# Light.net
KiCad netlist of a schematic drawn in Altium Designer
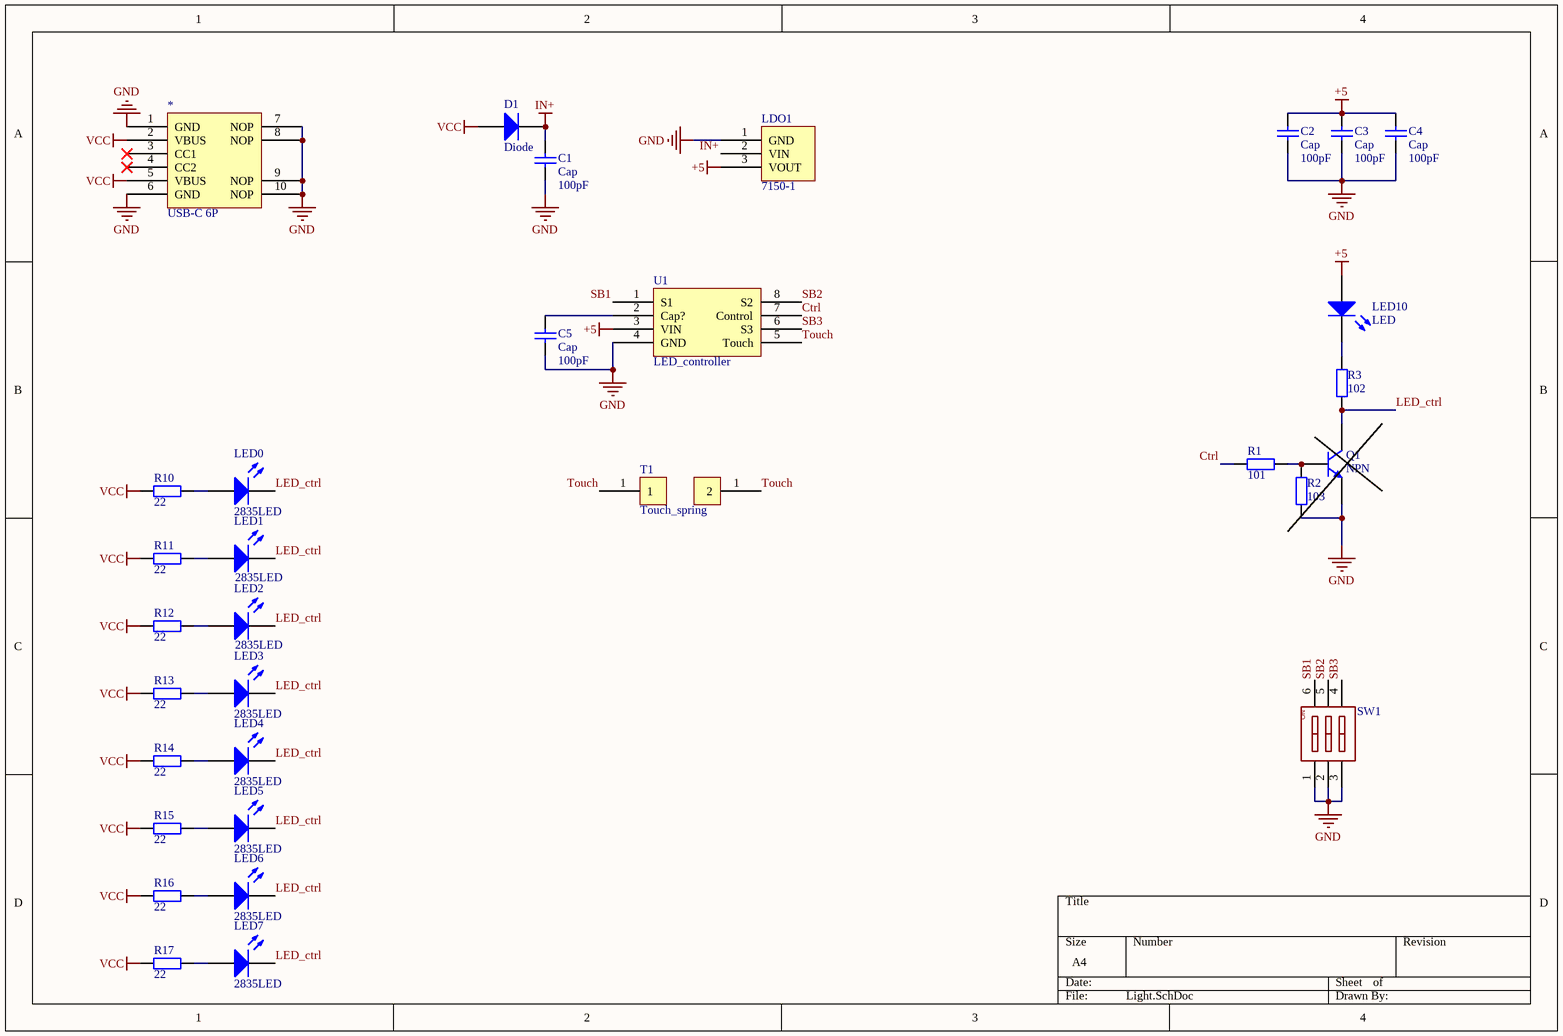
[diagram p0: Light.SchDoc]

(export (version "E")
  (design (tool "Eeschema 10.0.6"))
  (components
    (comp (ref "*") (value "USB-C 6P") (footprint "USB-C 6P") (libsource (lib "USB") (part "USB-C 6P")))
    (comp (ref "C1")
      (value "Cap")
      (footprint "6-0805_M")
      (description "Capacitor")
      (fields (field (name "ALTIUM_VALUE") "100pF") (field (name "PUBLISHER") "Altium Limited"))
      (libsource (lib "Miscellaneous Devices") (part "Cap"))
    )
    (comp (ref "C2")
      (value "Cap")
      (footprint "1608[0603]")
      (description "Capacitor")
      (fields (field (name "ALTIUM_VALUE") "100pF") (field (name "PUBLISHER") "Altium Limited"))
      (libsource (lib "Miscellaneous Devices") (part "Cap"))
    )
    (comp (ref "C3")
      (value "Cap")
      (footprint "1608[0603]")
      (description "Capacitor")
      (fields (field (name "ALTIUM_VALUE") "100pF") (field (name "PUBLISHER") "Altium Limited"))
      (libsource (lib "Miscellaneous Devices") (part "Cap"))
    )
    (comp (ref "C4")
      (value "Cap")
      (footprint "1608[0603]")
      (description "Capacitor")
      (fields (field (name "ALTIUM_VALUE") "100pF") (field (name "PUBLISHER") "Altium Limited"))
      (libsource (lib "Miscellaneous Devices") (part "Cap"))
    )
    (comp (ref "C5")
      (value "Cap")
      (footprint "1608[0603]")
      (description "Capacitor")
      (fields (field (name "ALTIUM_VALUE") "100pF") (field (name "PUBLISHER") "Altium Limited"))
      (libsource (lib "Miscellaneous Devices") (part "Cap"))
    )
    (comp (ref "D1")
      (value "Diode")
      (footprint "SOD-123")
      (description "Default Diode")
      (fields (field (name "PUBLISHER") "Altium Limited"))
      (libsource (lib "Miscellaneous Devices") (part "Diode"))
    )
    (comp (ref "LDO1")
      (value "7150-1")
      (footprint "SOT-89")
      (libsource (lib "Common_Modules") (part "7150-1"))
    )
    (comp (ref "LED0")
      (value "2835LED")
      (footprint "2835LED")
      (libsource (lib "Common_Modules") (part "2835LED"))
    )
    (comp (ref "LED1")
      (value "2835LED")
      (footprint "2835LED")
      (libsource (lib "Common_Modules") (part "2835LED"))
    )
    (comp (ref "LED2")
      (value "2835LED")
      (footprint "2835LED")
      (libsource (lib "Common_Modules") (part "2835LED"))
    )
    (comp (ref "LED3")
      (value "2835LED")
      (footprint "2835LED")
      (libsource (lib "Common_Modules") (part "2835LED"))
    )
    (comp (ref "LED4")
      (value "2835LED")
      (footprint "2835LED")
      (libsource (lib "Common_Modules") (part "2835LED"))
    )
    (comp (ref "LED5")
      (value "2835LED")
      (footprint "2835LED")
      (libsource (lib "Common_Modules") (part "2835LED"))
    )
    (comp (ref "LED6")
      (value "2835LED")
      (footprint "2835LED")
      (libsource (lib "Common_Modules") (part "2835LED"))
    )
    (comp (ref "LED7")
      (value "2835LED")
      (footprint "2835LED")
      (libsource (lib "Common_Modules") (part "2835LED"))
    )
    (comp (ref "LED10")
      (value "LED")
      (footprint "LED")
      (description "Typical INFRARED GaAs LED")
      (fields (field (name "PUBLISHER") "Altium Limited"))
      (libsource (lib "Miscellaneous Devices") (part "LED"))
    )
    (comp (ref "Q1")
      (value "NPN")
      (footprint "SOT23")
      (description "NPN Bipolar Transistor")
      (fields (field (name "PUBLISHER") "Altium Limited"))
      (libsource (lib "Miscellaneous Devices") (part "NPN"))
    )
    (comp (ref "R1")
      (value "101")
      (footprint "1608[0603]")
      (description "Resistor")
      (fields (field (name "PUBLISHER") "Altium Limited"))
      (libsource (lib "") (part "Res_1"))
    )
    (comp (ref "R2")
      (value "103")
      (footprint "1608[0603]")
      (description "Resistor")
      (fields (field (name "PUBLISHER") "Altium Limited"))
      (libsource (lib "Miscellaneous Devices") (part "Res"))
    )
    (comp (ref "R3")
      (value "102")
      (footprint "1608[0603]")
      (description "Resistor")
      (fields (field (name "PUBLISHER") "Altium Limited"))
      (libsource (lib "") (part "Res_2"))
    )
    (comp (ref "R10")
      (value "22")
      (footprint "R1206")
      (description "Resistor")
      (fields (field (name "PUBLISHER") "Altium Limited"))
      (libsource (lib "") (part "Res_1"))
    )
    (comp (ref "R11")
      (value "22")
      (footprint "R1206")
      (description "Resistor")
      (fields (field (name "PUBLISHER") "Altium Limited"))
      (libsource (lib "") (part "Res_1"))
    )
    (comp (ref "R12")
      (value "22")
      (footprint "R1206")
      (description "Resistor")
      (fields (field (name "PUBLISHER") "Altium Limited"))
      (libsource (lib "") (part "Res_1"))
    )
    (comp (ref "R13")
      (value "22")
      (footprint "R1206")
      (description "Resistor")
      (fields (field (name "PUBLISHER") "Altium Limited"))
      (libsource (lib "") (part "Res_1"))
    )
    (comp (ref "R14")
      (value "22")
      (footprint "R1206")
      (description "Resistor")
      (fields (field (name "PUBLISHER") "Altium Limited"))
      (libsource (lib "") (part "Res_1"))
    )
    (comp (ref "R15")
      (value "22")
      (footprint "R1206")
      (description "Resistor")
      (fields (field (name "PUBLISHER") "Altium Limited"))
      (libsource (lib "") (part "Res_1"))
    )
    (comp (ref "R16")
      (value "22")
      (footprint "R1206")
      (description "Resistor")
      (fields (field (name "PUBLISHER") "Altium Limited"))
      (libsource (lib "") (part "Res_1"))
    )
    (comp (ref "R17")
      (value "22")
      (footprint "R1206")
      (description "Resistor")
      (fields (field (name "PUBLISHER") "Altium Limited"))
      (libsource (lib "") (part "Res_1"))
    )
    (comp (ref "SW1")
      (value "SD03H0SB")
      (footprint "SW-SMD_3")
      (libsource (lib "Miscellaneous Devices") (part "SW Dial-3"))
    )
    (comp (ref "T1")
      (value "Touch_spring")
      (footprint "Touch_spring2")
      (libsource (lib "Connectivity_pads") (part "Touch_spring"))
    )
    (comp (ref "U1")
      (value "LED_controller")
      (footprint "SOP8")
      (libsource (lib "Common_Modules") (part "LED_controller"))
    )
  )
  (nets
    (net (code "1") (name "+5") (class "Default")
      (node (ref "C2") (pin "2") (pinfunction "2_2") (pintype "passive"))
      (node (ref "C3") (pin "2") (pinfunction "2_2") (pintype "passive"))
      (node (ref "C4") (pin "2") (pinfunction "2_2") (pintype "passive"))
      (node (ref "LDO1") (pin "3") (pinfunction "VOUT_3") (pintype "passive"))
      (node (ref "LED10") (pin "1") (pinfunction "A_1") (pintype "passive"))
      (node (ref "U1") (pin "3") (pinfunction "VIN_3") (pintype "passive"))
    )
    (net (code "2") (name "/Ctrl") (class "Default")
      (node (ref "R1") (pin "1") (pinfunction "1_1") (pintype "passive"))
      (node (ref "U1") (pin "7") (pinfunction "Control_7") (pintype "passive"))
    )
    (net (code "3") (name "/LED_ctrl") (class "Default")
      (node (ref "LED0") (pin "2") (pinfunction "K_2") (pintype "passive"))
      (node (ref "LED1") (pin "2") (pinfunction "K_2") (pintype "passive"))
      (node (ref "LED2") (pin "2") (pinfunction "K_2") (pintype "passive"))
      (node (ref "LED3") (pin "2") (pinfunction "K_2") (pintype "passive"))
      (node (ref "LED4") (pin "2") (pinfunction "K_2") (pintype "passive"))
      (node (ref "LED5") (pin "2") (pinfunction "K_2") (pintype "passive"))
      (node (ref "LED6") (pin "2") (pinfunction "K_2") (pintype "passive"))
      (node (ref "LED7") (pin "2") (pinfunction "K_2") (pintype "passive"))
      (node (ref "Q1") (pin "1") (pinfunction "C_1") (pintype "passive"))
      (node (ref "R3") (pin "2") (pinfunction "2_2") (pintype "passive"))
    )
    (net (code "4") (name "/SB1") (class "Default")
      (node (ref "SW1") (pin "6") (pinfunction "A6_6") (pintype "passive"))
      (node (ref "U1") (pin "1") (pinfunction "S1_1") (pintype "passive"))
    )
    (net (code "5") (name "/SB2") (class "Default")
      (node (ref "SW1") (pin "5") (pinfunction "A5_5") (pintype "passive"))
      (node (ref "U1") (pin "8") (pinfunction "S2_8") (pintype "passive"))
    )
    (net (code "6") (name "/SB3") (class "Default")
      (node (ref "SW1") (pin "4") (pinfunction "A4_4") (pintype "passive"))
      (node (ref "U1") (pin "6") (pinfunction "S3_6") (pintype "passive"))
    )
    (net (code "7") (name "/Touch") (class "Default")
      (node (ref "T1") (pin "1") (pinfunction "1_1") (pintype "passive"))
      (node (ref "U1") (pin "5") (pinfunction "Touch_5") (pintype "passive"))
    )
    (net (code "8") (name "GND") (class "Default")
      (node (ref "*") (pin "1") (pinfunction "GND_1") (pintype "passive"))
      (node (ref "*") (pin "10") (pinfunction "NOP_10") (pintype "passive"))
      (node (ref "*") (pin "6") (pinfunction "GND_6") (pintype "passive"))
      (node (ref "*") (pin "7") (pinfunction "NOP_7") (pintype "passive"))
      (node (ref "*") (pin "8") (pinfunction "NOP_8") (pintype "passive"))
      (node (ref "*") (pin "9") (pinfunction "NOP_9") (pintype "passive"))
      (node (ref "C1") (pin "1") (pinfunction "1_1") (pintype "passive"))
      (node (ref "C2") (pin "1") (pinfunction "1_1") (pintype "passive"))
      (node (ref "C3") (pin "1") (pinfunction "1_1") (pintype "passive"))
      (node (ref "C4") (pin "1") (pinfunction "1_1") (pintype "passive"))
      (node (ref "C5") (pin "1") (pinfunction "1_1") (pintype "passive"))
      (node (ref "LDO1") (pin "1") (pinfunction "GND_1") (pintype "passive"))
      (node (ref "Q1") (pin "3") (pinfunction "E_3") (pintype "passive"))
      (node (ref "R2") (pin "1") (pinfunction "1_1") (pintype "passive"))
      (node (ref "SW1") (pin "1") (pinfunction "A1_1") (pintype "passive"))
      (node (ref "SW1") (pin "2") (pinfunction "A2_2") (pintype "passive"))
      (node (ref "SW1") (pin "3") (pinfunction "A3_3") (pintype "passive"))
      (node (ref "U1") (pin "4") (pinfunction "GND_4") (pintype "passive"))
    )
    (net (code "9") (name "IN+") (class "Default")
      (node (ref "C1") (pin "2") (pinfunction "2_2") (pintype "passive"))
      (node (ref "D1") (pin "2") (pinfunction "K_2") (pintype "passive"))
      (node (ref "LDO1") (pin "2") (pinfunction "VIN_2") (pintype "passive"))
    )
    (net (code "10") (name "Net-(LED0-A)") (class "Default")
      (node (ref "LED0") (pin "1") (pinfunction "A_1") (pintype "passive"))
      (node (ref "R10") (pin "2") (pinfunction "2_2") (pintype "passive"))
    )
    (net (code "11") (name "Net-(LED1-A)") (class "Default")
      (node (ref "LED1") (pin "1") (pinfunction "A_1") (pintype "passive"))
      (node (ref "R11") (pin "2") (pinfunction "2_2") (pintype "passive"))
    )
    (net (code "12") (name "Net-(LED2-A)") (class "Default")
      (node (ref "LED2") (pin "1") (pinfunction "A_1") (pintype "passive"))
      (node (ref "R12") (pin "2") (pinfunction "2_2") (pintype "passive"))
    )
    (net (code "13") (name "Net-(LED3-A)") (class "Default")
      (node (ref "LED3") (pin "1") (pinfunction "A_1") (pintype "passive"))
      (node (ref "R13") (pin "2") (pinfunction "2_2") (pintype "passive"))
    )
    (net (code "14") (name "Net-(LED4-A)") (class "Default")
      (node (ref "LED4") (pin "1") (pinfunction "A_1") (pintype "passive"))
      (node (ref "R14") (pin "2") (pinfunction "2_2") (pintype "passive"))
    )
    (net (code "15") (name "Net-(LED5-A)") (class "Default")
      (node (ref "LED5") (pin "1") (pinfunction "A_1") (pintype "passive"))
      (node (ref "R15") (pin "2") (pinfunction "2_2") (pintype "passive"))
    )
    (net (code "16") (name "Net-(LED6-A)") (class "Default")
      (node (ref "LED6") (pin "1") (pinfunction "A_1") (pintype "passive"))
      (node (ref "R16") (pin "2") (pinfunction "2_2") (pintype "passive"))
    )
    (net (code "17") (name "Net-(LED7-A)") (class "Default")
      (node (ref "LED7") (pin "1") (pinfunction "A_1") (pintype "passive"))
      (node (ref "R17") (pin "2") (pinfunction "2_2") (pintype "passive"))
    )
    (net (code "18") (name "Net-(LED10-K)") (class "Default")
      (node (ref "LED10") (pin "2") (pinfunction "K_2") (pintype "passive"))
      (node (ref "R3") (pin "1") (pinfunction "1_1") (pintype "passive"))
    )
    (net (code "19") (name "Net-(Q1-B)") (class "Default")
      (node (ref "Q1") (pin "2") (pinfunction "B_2") (pintype "passive"))
      (node (ref "R1") (pin "2") (pinfunction "2_2") (pintype "passive"))
      (node (ref "R2") (pin "2") (pinfunction "2_2") (pintype "passive"))
    )
    (net (code "20") (name "Net-(U1-Cap?)") (class "Default")
      (node (ref "C5") (pin "2") (pinfunction "2_2") (pintype "passive"))
      (node (ref "U1") (pin "2") (pinfunction "Cap?_2") (pintype "passive"))
    )
    (net (code "21") (name "VCC") (class "Default")
      (node (ref "*") (pin "2") (pinfunction "VBUS_2") (pintype "passive"))
      (node (ref "*") (pin "5") (pinfunction "VBUS_5") (pintype "passive"))
      (node (ref "D1") (pin "1") (pinfunction "A_1") (pintype "passive"))
      (node (ref "R10") (pin "1") (pinfunction "1_1") (pintype "passive"))
      (node (ref "R11") (pin "1") (pinfunction "1_1") (pintype "passive"))
      (node (ref "R12") (pin "1") (pinfunction "1_1") (pintype "passive"))
      (node (ref "R13") (pin "1") (pinfunction "1_1") (pintype "passive"))
      (node (ref "R14") (pin "1") (pinfunction "1_1") (pintype "passive"))
      (node (ref "R15") (pin "1") (pinfunction "1_1") (pintype "passive"))
      (node (ref "R16") (pin "1") (pinfunction "1_1") (pintype "passive"))
      (node (ref "R17") (pin "1") (pinfunction "1_1") (pintype "passive"))
    )
    (net (code "22") (name "unconnected-(*-CC1-Pad3)") (class "Default")
      (node (ref "*") (pin "3") (pinfunction "CC1_3") (pintype "passive+no_connect"))
    )
    (net (code "23") (name "unconnected-(*-CC2-Pad4)") (class "Default")
      (node (ref "*") (pin "4") (pinfunction "CC2_4") (pintype "passive+no_connect"))
    )
  )
)
